# RJ-45_v1_1_Top_Routed.net
KiCad netlist of a schematic drawn in EAGLE
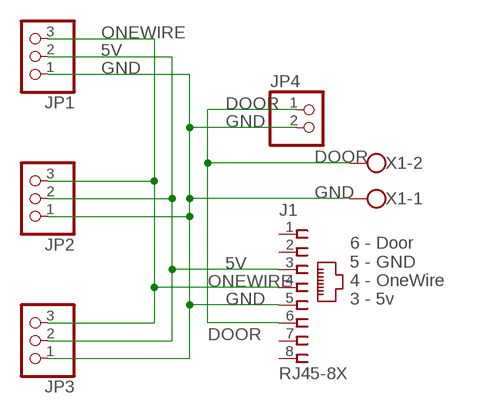
[diagram p0: schematic, sheet 1]

(export (version "E")
  (design (tool "Eeschema 10.0.6"))
  (components
    (comp (ref "J1")
      (value "RJ45-8X")
      (footprint "eagle-import:RJ45-NO-SHIELD")
      (libsource (lib "eagle-import") (part "RJ45-8X"))
    )
    (comp (ref "JP1")
      (value "PINHD-1X3")
      (footprint "eagle-import:1X03")
      (libsource (lib "eagle-import") (part "PINHD-1X3"))
    )
    (comp (ref "JP2")
      (value "PINHD-1X3")
      (footprint "eagle-import:1X03")
      (libsource (lib "eagle-import") (part "PINHD-1X3"))
    )
    (comp (ref "JP3")
      (value "PINHD-1X3")
      (footprint "eagle-import:1X03")
      (libsource (lib "eagle-import") (part "PINHD-1X3"))
    )
    (comp (ref "JP4")
      (value "PINHD-1X2")
      (footprint "eagle-import:1X02")
      (libsource (lib "eagle-import") (part "PINHD-1X2"))
    )
    (comp (ref "X1")
      (value "W237-102")
      (footprint "eagle-import:W237-102")
      (fields (field (name "MPN") "237-102"))
      (libsource (lib "eagle-import") (part "W237-102"))
    )
  )
  (nets
    (net (code "1") (name "/5V") (class "Default")
      (node (ref "J1") (pin "3") (pinfunction "3_3") (pintype "passive"))
      (node (ref "JP1") (pin "2") (pinfunction "2_2") (pintype "passive"))
      (node (ref "JP2") (pin "2") (pinfunction "2_2") (pintype "passive"))
      (node (ref "JP3") (pin "2") (pinfunction "2_2") (pintype "passive"))
    )
    (net (code "2") (name "/DOOR") (class "Default")
      (node (ref "J1") (pin "6") (pinfunction "6_6") (pintype "passive"))
      (node (ref "JP4") (pin "1") (pinfunction "1_1") (pintype "passive"))
      (node (ref "X1") (pin "2") (pinfunction "KL_2") (pintype "passive"))
    )
    (net (code "3") (name "/GND") (class "Default")
      (node (ref "J1") (pin "5") (pinfunction "5_5") (pintype "passive"))
      (node (ref "JP1") (pin "1") (pinfunction "1_1") (pintype "passive"))
      (node (ref "JP2") (pin "1") (pinfunction "1_1") (pintype "passive"))
      (node (ref "JP3") (pin "1") (pinfunction "1_1") (pintype "passive"))
      (node (ref "JP4") (pin "2") (pinfunction "2_2") (pintype "passive"))
      (node (ref "X1") (pin "1") (pinfunction "KL_1") (pintype "passive"))
    )
    (net (code "4") (name "/ONEWIRE") (class "Default")
      (node (ref "J1") (pin "4") (pinfunction "4_4") (pintype "passive"))
      (node (ref "JP1") (pin "3") (pinfunction "3_3") (pintype "passive"))
      (node (ref "JP2") (pin "3") (pinfunction "3_3") (pintype "passive"))
      (node (ref "JP3") (pin "3") (pinfunction "3_3") (pintype "passive"))
    )
    (net (code "5") (name "unconnected-(J1-Pad1)") (class "Default")
      (node (ref "J1") (pin "1") (pinfunction "1_1") (pintype "passive"))
    )
    (net (code "6") (name "unconnected-(J1-Pad2)") (class "Default")
      (node (ref "J1") (pin "2") (pinfunction "2_2") (pintype "passive"))
    )
    (net (code "7") (name "unconnected-(J1-Pad7)") (class "Default")
      (node (ref "J1") (pin "7") (pinfunction "7_7") (pintype "passive"))
    )
    (net (code "8") (name "unconnected-(J1-Pad8)") (class "Default")
      (node (ref "J1") (pin "8") (pinfunction "8_8") (pintype "passive"))
    )
  )
)
